# Controls_Microcontroller.net
KiCad netlist of a schematic drawn in Altium Designer
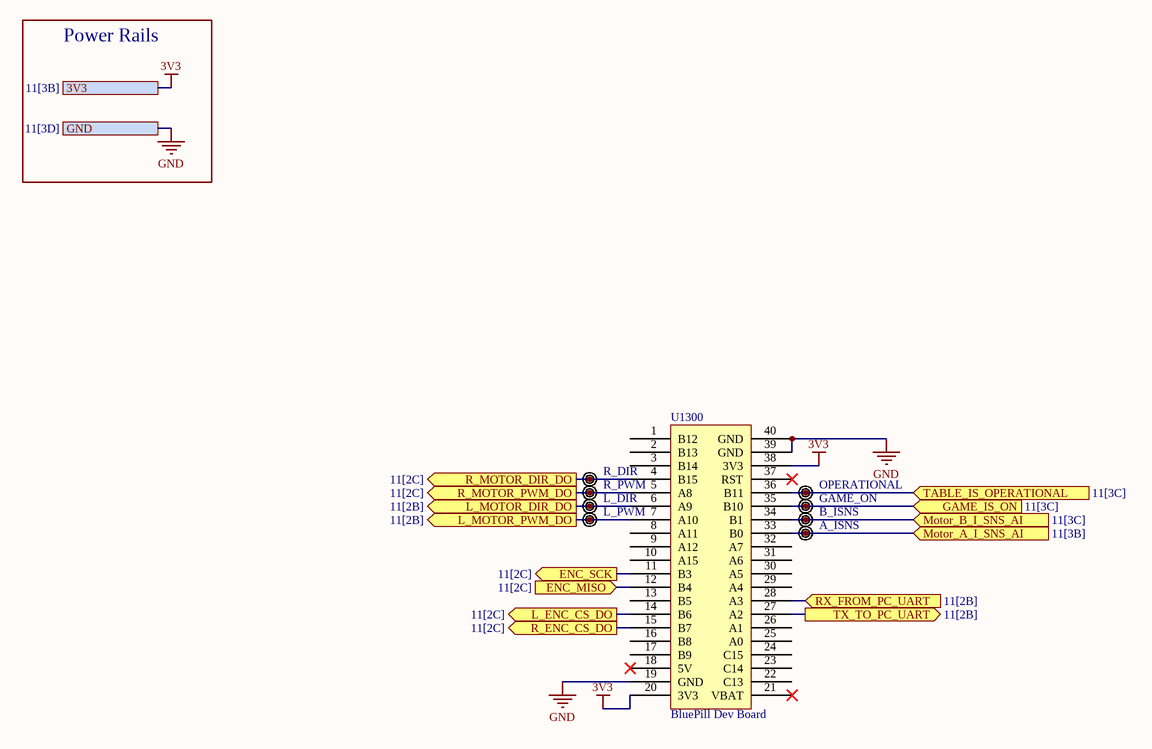
[diagram p0: Controls_Microcontroller.SchDoc]

(export (version "E")
  (design (tool "Eeschema 10.0.6"))
  (components
    (comp (ref "TP1300")
      (value "R_DIR")
      (footprint "TESTPOINT")
      (fields (field (name "SOURCE") "UBC Formula Electric.SchLib"))
      (libsource (lib "UBC Formula Electric") (part "Thru-Hole Test Point"))
    )
    (comp (ref "TP1301")
      (value "R_PWM")
      (footprint "TESTPOINT")
      (fields (field (name "SOURCE") "UBC Formula Electric.SchLib"))
      (libsource (lib "UBC Formula Electric") (part "Thru-Hole Test Point"))
    )
    (comp (ref "TP1302")
      (value "OPERATIONAL")
      (footprint "TESTPOINT")
      (fields (field (name "SOURCE") "UBC Formula Electric.SchLib"))
      (libsource (lib "UBC Formula Electric") (part "Thru-Hole Test Point"))
    )
    (comp (ref "TP1303")
      (value "L_DIR")
      (footprint "TESTPOINT")
      (fields (field (name "SOURCE") "UBC Formula Electric.SchLib"))
      (libsource (lib "UBC Formula Electric") (part "Thru-Hole Test Point"))
    )
    (comp (ref "TP1304")
      (value "GAME_ON")
      (footprint "TESTPOINT")
      (fields (field (name "SOURCE") "UBC Formula Electric.SchLib"))
      (libsource (lib "UBC Formula Electric") (part "Thru-Hole Test Point"))
    )
    (comp (ref "TP1305")
      (value "L_PWM")
      (footprint "TESTPOINT")
      (fields (field (name "SOURCE") "UBC Formula Electric.SchLib"))
      (libsource (lib "UBC Formula Electric") (part "Thru-Hole Test Point"))
    )
    (comp (ref "TP1306")
      (value "B_ISNS")
      (footprint "TESTPOINT")
      (fields (field (name "SOURCE") "UBC Formula Electric.SchLib"))
      (libsource (lib "UBC Formula Electric") (part "Thru-Hole Test Point"))
    )
    (comp (ref "TP1307")
      (value "A_ISNS")
      (footprint "TESTPOINT")
      (fields (field (name "SOURCE") "UBC Formula Electric.SchLib"))
      (libsource (lib "UBC Formula Electric") (part "Thru-Hole Test Point"))
    )
    (comp (ref "U1300")
      (value "BluePill Dev Board")
      (footprint "Blue Pill")
      (libsource (lib "air_hockey_lib") (part "BluePill Dev Board"))
    )
  )
  (nets
    (net (code "1") (name "/ENC_MISO") (class "Default")
      (node (ref "U1300") (pin "12") (pinfunction "B4_12") (pintype "passive"))
    )
    (net (code "2") (name "/ENC_SCK") (class "Default")
      (node (ref "U1300") (pin "11") (pinfunction "B3_11") (pintype "passive"))
    )
    (net (code "3") (name "/GAME_IS_ON") (class "Default")
      (node (ref "TP1304") (pin "1") (pinfunction "TP_1") (pintype "passive"))
      (node (ref "U1300") (pin "35") (pinfunction "B10_35") (pintype "passive"))
    )
    (net (code "4") (name "/L_ENC_CS_DO") (class "Default")
      (node (ref "U1300") (pin "14") (pinfunction "B6_14") (pintype "passive"))
    )
    (net (code "5") (name "/L_MOTOR_DIR_DO") (class "Default")
      (node (ref "TP1303") (pin "1") (pinfunction "TP_1") (pintype "passive"))
      (node (ref "U1300") (pin "6") (pinfunction "A9_6") (pintype "passive"))
    )
    (net (code "6") (name "/L_MOTOR_PWM_DO") (class "Default")
      (node (ref "TP1305") (pin "1") (pinfunction "TP_1") (pintype "passive"))
      (node (ref "U1300") (pin "7") (pinfunction "A10_7") (pintype "passive"))
    )
    (net (code "7") (name "/Motor_A_I_SNS_AI") (class "Default")
      (node (ref "TP1307") (pin "1") (pinfunction "TP_1") (pintype "passive"))
      (node (ref "U1300") (pin "33") (pinfunction "B0_33") (pintype "passive"))
    )
    (net (code "8") (name "/Motor_B_I_SNS_AI") (class "Default")
      (node (ref "TP1306") (pin "1") (pinfunction "TP_1") (pintype "passive"))
      (node (ref "U1300") (pin "34") (pinfunction "B1_34") (pintype "passive"))
    )
    (net (code "9") (name "/RX_FROM_PC_UART") (class "Default")
      (node (ref "U1300") (pin "28") (pinfunction "A3_28") (pintype "passive"))
    )
    (net (code "10") (name "/R_ENC_CS_DO") (class "Default")
      (node (ref "U1300") (pin "15") (pinfunction "B7_15") (pintype "passive"))
    )
    (net (code "11") (name "/R_MOTOR_DIR_DO") (class "Default")
      (node (ref "TP1300") (pin "1") (pinfunction "TP_1") (pintype "passive"))
      (node (ref "U1300") (pin "4") (pinfunction "B15_4") (pintype "passive"))
    )
    (net (code "12") (name "/R_MOTOR_PWM_DO") (class "Default")
      (node (ref "TP1301") (pin "1") (pinfunction "TP_1") (pintype "passive"))
      (node (ref "U1300") (pin "5") (pinfunction "A8_5") (pintype "passive"))
    )
    (net (code "13") (name "/TABLE_IS_OPERATIONAL") (class "Default")
      (node (ref "TP1302") (pin "1") (pinfunction "TP_1") (pintype "passive"))
      (node (ref "U1300") (pin "36") (pinfunction "B11_36") (pintype "passive"))
    )
    (net (code "14") (name "/TX_TO_PC_UART") (class "Default")
      (node (ref "U1300") (pin "27") (pinfunction "A2_27") (pintype "passive"))
    )
    (net (code "15") (name "3V3") (class "Default")
      (node (ref "U1300") (pin "20") (pinfunction "3V3_20") (pintype "passive"))
      (node (ref "U1300") (pin "38") (pinfunction "3V3_38") (pintype "passive"))
    )
    (net (code "16") (name "GND") (class "Default")
      (node (ref "U1300") (pin "19") (pinfunction "GND_19") (pintype "passive"))
      (node (ref "U1300") (pin "39") (pinfunction "GND_39") (pintype "passive"))
      (node (ref "U1300") (pin "40") (pinfunction "GND_40") (pintype "passive"))
    )
    (net (code "17") (name "unconnected-(U1300-5V-Pad18)") (class "Default")
      (node (ref "U1300") (pin "18") (pinfunction "5V_18") (pintype "passive+no_connect"))
    )
    (net (code "18") (name "unconnected-(U1300-A0-Pad25)") (class "Default")
      (node (ref "U1300") (pin "25") (pinfunction "A0_25") (pintype "passive"))
    )
    (net (code "19") (name "unconnected-(U1300-A1-Pad26)") (class "Default")
      (node (ref "U1300") (pin "26") (pinfunction "A1_26") (pintype "passive"))
    )
    (net (code "20") (name "unconnected-(U1300-A4-Pad29)") (class "Default")
      (node (ref "U1300") (pin "29") (pinfunction "A4_29") (pintype "passive"))
    )
    (net (code "21") (name "unconnected-(U1300-A5-Pad30)") (class "Default")
      (node (ref "U1300") (pin "30") (pinfunction "A5_30") (pintype "passive"))
    )
    (net (code "22") (name "unconnected-(U1300-A6-Pad31)") (class "Default")
      (node (ref "U1300") (pin "31") (pinfunction "A6_31") (pintype "passive"))
    )
    (net (code "23") (name "unconnected-(U1300-A7-Pad32)") (class "Default")
      (node (ref "U1300") (pin "32") (pinfunction "A7_32") (pintype "passive"))
    )
    (net (code "24") (name "unconnected-(U1300-A11-Pad8)") (class "Default")
      (node (ref "U1300") (pin "8") (pinfunction "A11_8") (pintype "passive"))
    )
    (net (code "25") (name "unconnected-(U1300-A12-Pad9)") (class "Default")
      (node (ref "U1300") (pin "9") (pinfunction "A12_9") (pintype "passive"))
    )
    (net (code "26") (name "unconnected-(U1300-A15-Pad10)") (class "Default")
      (node (ref "U1300") (pin "10") (pinfunction "A15_10") (pintype "passive"))
    )
    (net (code "27") (name "unconnected-(U1300-B5-Pad13)") (class "Default")
      (node (ref "U1300") (pin "13") (pinfunction "B5_13") (pintype "passive"))
    )
    (net (code "28") (name "unconnected-(U1300-B8-Pad16)") (class "Default")
      (node (ref "U1300") (pin "16") (pinfunction "B8_16") (pintype "passive"))
    )
    (net (code "29") (name "unconnected-(U1300-B9-Pad17)") (class "Default")
      (node (ref "U1300") (pin "17") (pinfunction "B9_17") (pintype "passive"))
    )
    (net (code "30") (name "unconnected-(U1300-B12-Pad1)") (class "Default")
      (node (ref "U1300") (pin "1") (pinfunction "B12_1") (pintype "passive"))
    )
    (net (code "31") (name "unconnected-(U1300-B13-Pad2)") (class "Default")
      (node (ref "U1300") (pin "2") (pinfunction "B13_2") (pintype "passive"))
    )
    (net (code "32") (name "unconnected-(U1300-B14-Pad3)") (class "Default")
      (node (ref "U1300") (pin "3") (pinfunction "B14_3") (pintype "passive"))
    )
    (net (code "33") (name "unconnected-(U1300-C13-Pad22)") (class "Default")
      (node (ref "U1300") (pin "22") (pinfunction "C13_22") (pintype "passive"))
    )
    (net (code "34") (name "unconnected-(U1300-C14-Pad23)") (class "Default")
      (node (ref "U1300") (pin "23") (pinfunction "C14_23") (pintype "passive"))
    )
    (net (code "35") (name "unconnected-(U1300-C15-Pad24)") (class "Default")
      (node (ref "U1300") (pin "24") (pinfunction "C15_24") (pintype "passive"))
    )
    (net (code "36") (name "unconnected-(U1300-RST-Pad37)") (class "Default")
      (node (ref "U1300") (pin "37") (pinfunction "RST_37") (pintype "passive+no_connect"))
    )
    (net (code "37") (name "unconnected-(U1300-VBAT-Pad21)") (class "Default")
      (node (ref "U1300") (pin "21") (pinfunction "VBAT_21") (pintype "passive+no_connect"))
    )
  )
)
